# 24_LMS2_RX2_BB_ADC.net
KiCad netlist of a schematic drawn in Altium Designer
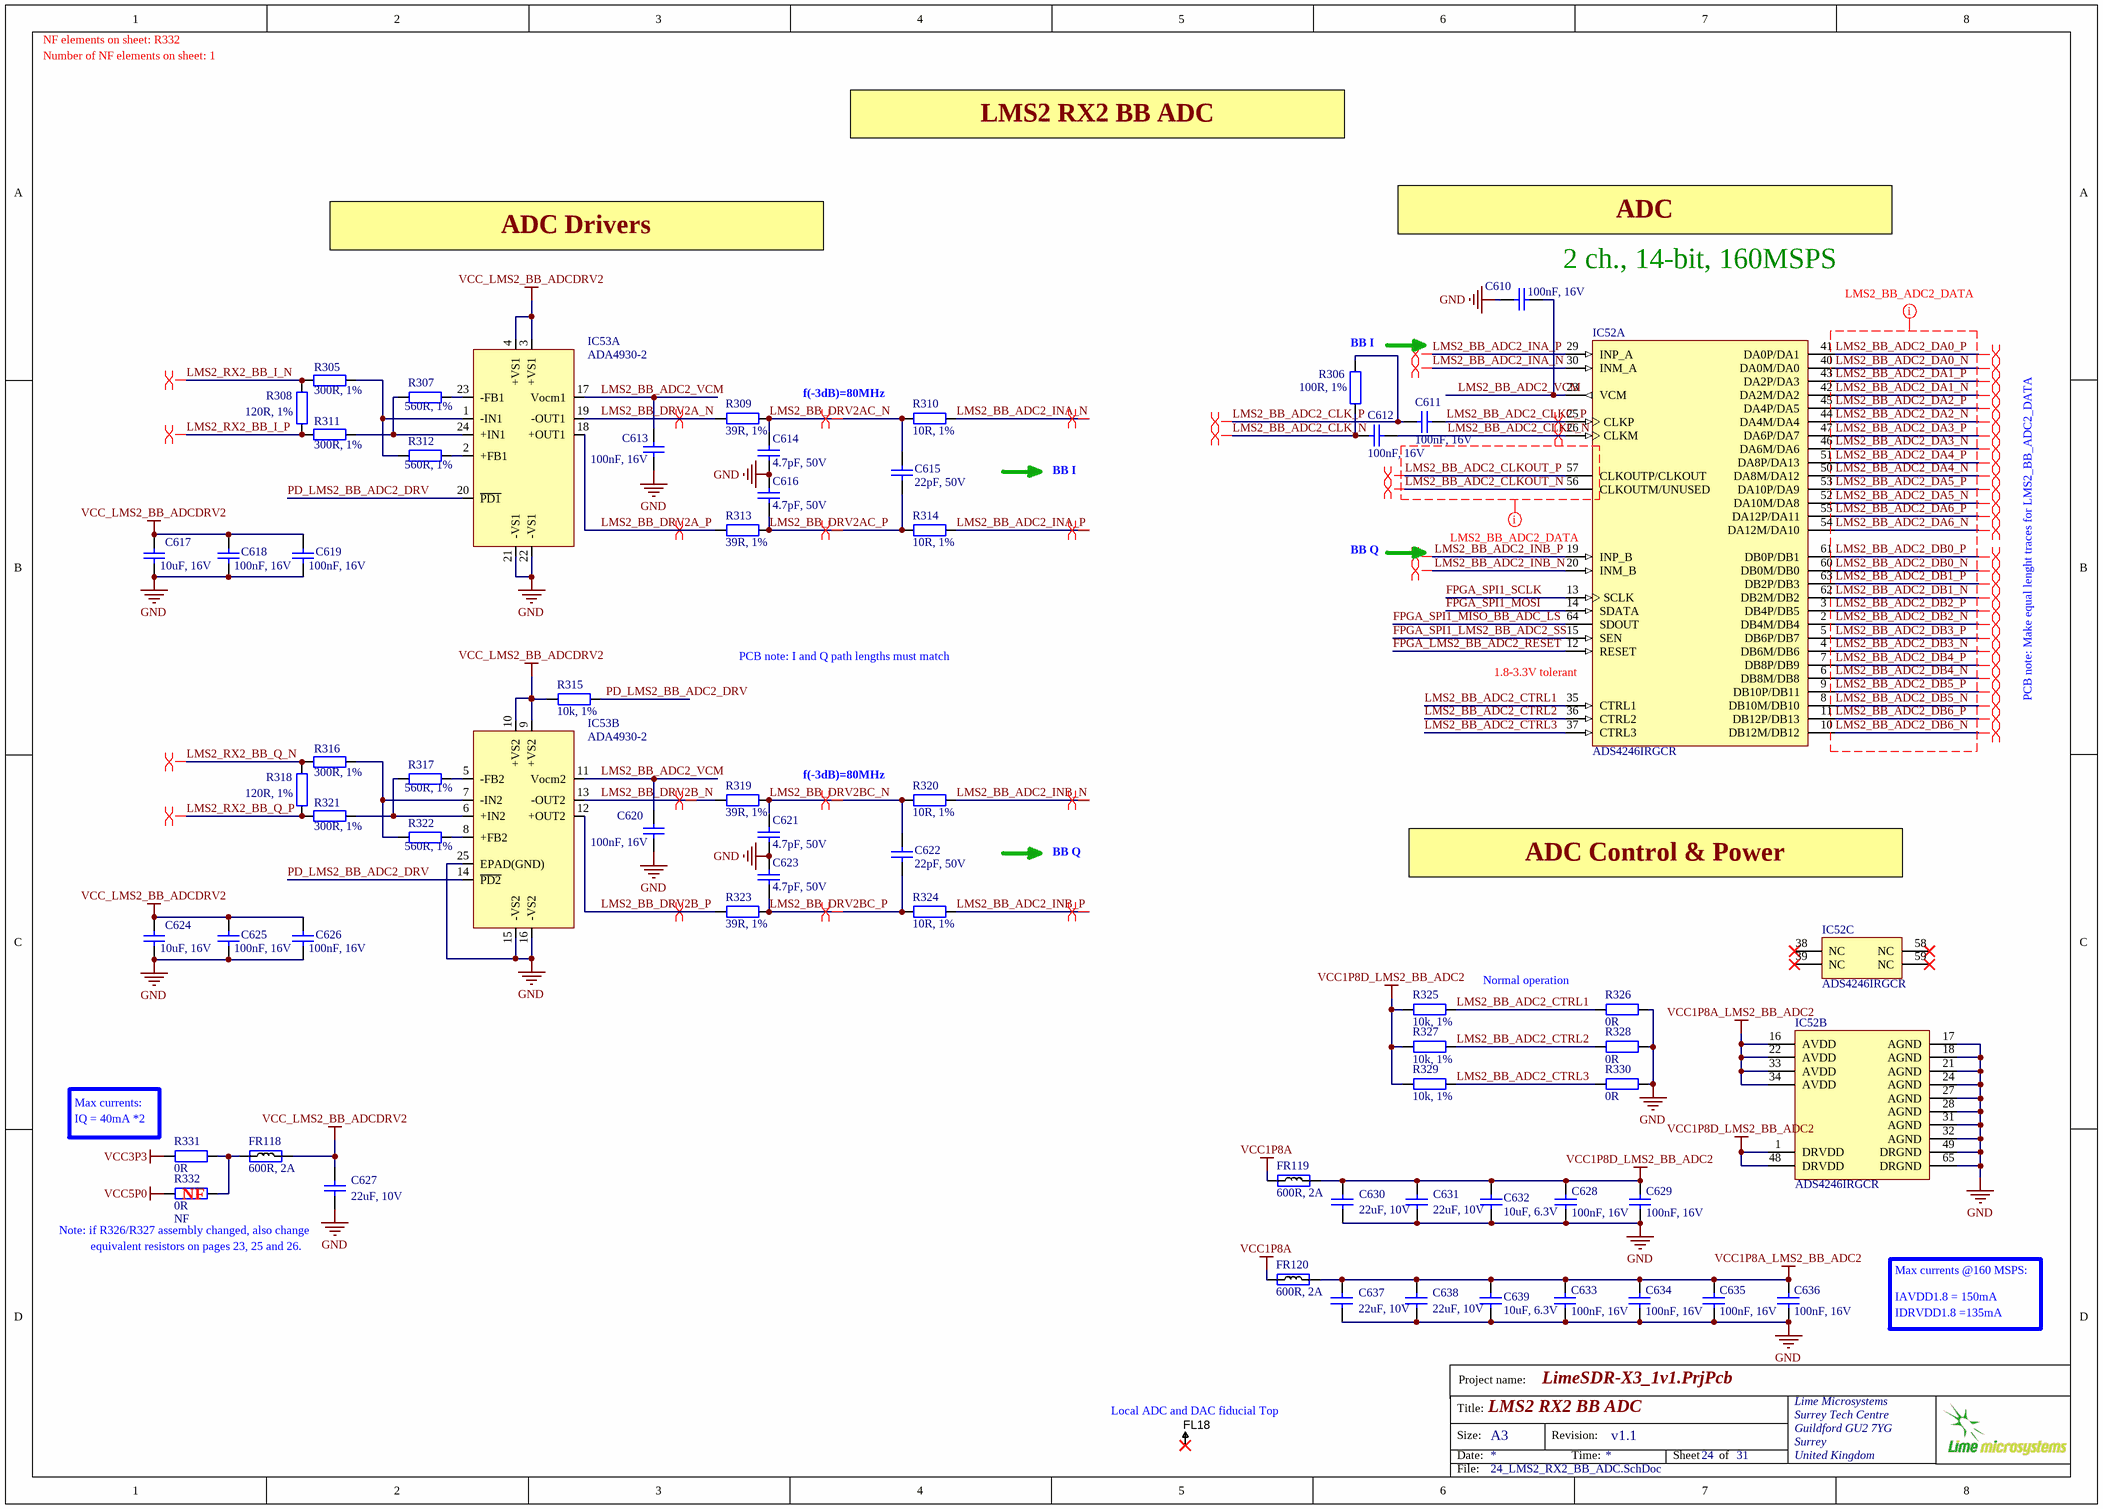
[diagram p0: 24_LMS2_RX2_BB_ADC.SchDoc]

(export (version "E")
  (design (tool "Eeschema 10.0.6"))
  (components
    (comp (ref "C610")
      (value "100nF, 16V")
      (footprint "CAP0402")
      (fields (field (name "TOLERANCE") "10 %") (field (name "MANUFACTURER") "Murata Electronics"))
      (libsource (lib "") (part "Cap_0603_6"))
    )
    (comp (ref "C611")
      (value "100nF, 16V")
      (footprint "CAP0402")
      (fields (field (name "TOLERANCE") "10 %") (field (name "MANUFACTURER") "Murata Electronics"))
      (libsource (lib "") (part "Cap_0603_6"))
    )
    (comp (ref "C612")
      (value "100nF, 16V")
      (footprint "CAP0402")
      (fields (field (name "TOLERANCE") "10 %") (field (name "MANUFACTURER") "Murata Electronics"))
      (libsource (lib "LimeFPGAboard_schLib") (part "Cap_0603"))
    )
    (comp (ref "C613")
      (value "100nF, 16V")
      (footprint "CAP0402")
      (fields (field (name "TOLERANCE") "10 %") (field (name "MANUFACTURER") "Murata Electronics"))
      (libsource (lib "LimeFPGAboard_schLib") (part "Cap_0603"))
    )
    (comp (ref "C614")
      (value "4.7pF, 50V")
      (footprint "CAP0402")
      (fields (field (name "MANUFACTURER") "MURATA"))
      (libsource (lib "LimeMicroAltiumLib_schLib") (part "Cap_0402"))
    )
    (comp (ref "C615")
      (value "22pF, 50V")
      (footprint "CAP0402")
      (fields (field (name "TOLERANCE") "±5%") (field (name "MANUFACTURER") "Yageo"))
      (libsource (lib "") (part "Cap_0402_1"))
    )
    (comp (ref "C616")
      (value "4.7pF, 50V")
      (footprint "CAP0402")
      (fields (field (name "MANUFACTURER") "MURATA"))
      (libsource (lib "LimeMicroAltiumLib_schLib") (part "Cap_0402"))
    )
    (comp (ref "C617")
      (value "10uF, 16V")
      (footprint "CAP0603")
      (fields (field (name "MANUFACTURER") "Yageo") (field (name "TOLERANCE") "±20%"))
      (libsource (lib "LimeMicroAltiumLib_schLib") (part "Cap_0603"))
    )
    (comp (ref "C618")
      (value "100nF, 16V")
      (footprint "CAP0402")
      (fields (field (name "TOLERANCE") "10 %") (field (name "MANUFACTURER") "Murata Electronics"))
      (libsource (lib "LimeFPGAboard_schLib") (part "Cap_0603"))
    )
    (comp (ref "C619")
      (value "100nF, 16V")
      (footprint "CAP0402")
      (fields (field (name "TOLERANCE") "10 %") (field (name "MANUFACTURER") "Murata Electronics"))
      (libsource (lib "LimeFPGAboard_schLib") (part "Cap_0603"))
    )
    (comp (ref "C620")
      (value "100nF, 16V")
      (footprint "CAP0402")
      (fields (field (name "TOLERANCE") "10 %") (field (name "MANUFACTURER") "Murata Electronics"))
      (libsource (lib "") (part "Cap_0603_5"))
    )
    (comp (ref "C621")
      (value "4.7pF, 50V")
      (footprint "CAP0402")
      (fields (field (name "MANUFACTURER") "MURATA"))
      (libsource (lib "LimeMicroAltiumLib_schLib") (part "Cap_0402"))
    )
    (comp (ref "C622")
      (value "22pF, 50V")
      (footprint "CAP0402")
      (fields (field (name "TOLERANCE") "±5%") (field (name "MANUFACTURER") "Yageo"))
      (libsource (lib "") (part "Cap_0402_1"))
    )
    (comp (ref "C623")
      (value "4.7pF, 50V")
      (footprint "CAP0402")
      (fields (field (name "MANUFACTURER") "MURATA"))
      (libsource (lib "LimeMicroAltiumLib_schLib") (part "Cap_0402"))
    )
    (comp (ref "C624")
      (value "10uF, 16V")
      (footprint "CAP0603")
      (fields (field (name "MANUFACTURER") "Yageo") (field (name "TOLERANCE") "±20%"))
      (libsource (lib "LimeMicroAltiumLib_schLib") (part "Cap_0603"))
    )
    (comp (ref "C625")
      (value "100nF, 16V")
      (footprint "CAP0402")
      (fields (field (name "TOLERANCE") "10 %") (field (name "MANUFACTURER") "Murata Electronics"))
      (libsource (lib "LimeFPGAboard_schLib") (part "Cap_0603"))
    )
    (comp (ref "C626")
      (value "100nF, 16V")
      (footprint "CAP0402")
      (fields (field (name "TOLERANCE") "10 %") (field (name "MANUFACTURER") "Murata Electronics"))
      (libsource (lib "LimeFPGAboard_schLib") (part "Cap_0603"))
    )
    (comp (ref "C627")
      (value "22uF, 10V")
      (footprint "CAP0603")
      (fields (field (name "TOLERANCE") "20 %") (field (name "MANUFACTURER") "TDK Corporation"))
      (libsource (lib "") (part "Cap_0603_3"))
    )
    (comp (ref "C628")
      (value "100nF, 16V")
      (footprint "CAP0402")
      (fields (field (name "TOLERANCE") "10 %") (field (name "MANUFACTURER") "Murata Electronics"))
      (libsource (lib "") (part "Cap_0603_1"))
    )
    (comp (ref "C629")
      (value "100nF, 16V")
      (footprint "CAP0402")
      (fields (field (name "TOLERANCE") "10 %") (field (name "MANUFACTURER") "Murata Electronics"))
      (libsource (lib "") (part "Cap_0603_1"))
    )
    (comp (ref "C630")
      (value "22uF, 10V")
      (footprint "CAP0603")
      (fields (field (name "TOLERANCE") "20 %") (field (name "MANUFACTURER") "TDK Corporation"))
      (libsource (lib "") (part "Cap_0603_1"))
    )
    (comp (ref "C631")
      (value "22uF, 10V")
      (footprint "CAP0603")
      (fields (field (name "TOLERANCE") "20 %") (field (name "MANUFACTURER") "TDK Corporation"))
      (libsource (lib "") (part "Cap_0603_1"))
    )
    (comp (ref "C632")
      (value "10uF, 6.3V")
      (footprint "CAP0603")
      (fields (field (name "TOLERANCE") "±20%") (field (name "MANUFACTURER") "Yageo"))
      (libsource (lib "") (part "Cap_0603_7"))
    )
    (comp (ref "C633")
      (value "100nF, 16V")
      (footprint "CAP0402")
      (fields (field (name "TOLERANCE") "10 %") (field (name "MANUFACTURER") "Murata Electronics"))
      (libsource (lib "") (part "Cap_0603_2"))
    )
    (comp (ref "C634")
      (value "100nF, 16V")
      (footprint "CAP0402")
      (fields (field (name "TOLERANCE") "10 %") (field (name "MANUFACTURER") "Murata Electronics"))
      (libsource (lib "") (part "Cap_0603_2"))
    )
    (comp (ref "C635")
      (value "100nF, 16V")
      (footprint "CAP0402")
      (fields (field (name "TOLERANCE") "10 %") (field (name "MANUFACTURER") "Murata Electronics"))
      (libsource (lib "") (part "Cap_0603_2"))
    )
    (comp (ref "C636")
      (value "100nF, 16V")
      (footprint "CAP0402")
      (fields (field (name "TOLERANCE") "10 %") (field (name "MANUFACTURER") "Murata Electronics"))
      (libsource (lib "") (part "Cap_0603_2"))
    )
    (comp (ref "C637")
      (value "22uF, 10V")
      (footprint "CAP0603")
      (fields (field (name "TOLERANCE") "20 %") (field (name "MANUFACTURER") "TDK Corporation"))
      (libsource (lib "") (part "Cap_0603_2"))
    )
    (comp (ref "C638")
      (value "22uF, 10V")
      (footprint "CAP0603")
      (fields (field (name "TOLERANCE") "20 %") (field (name "MANUFACTURER") "TDK Corporation"))
      (libsource (lib "") (part "Cap_0603_2"))
    )
    (comp (ref "C639")
      (value "10uF, 6.3V")
      (footprint "CAP0603")
      (fields (field (name "TOLERANCE") "±20%") (field (name "MANUFACTURER") "Yageo"))
      (libsource (lib "") (part "Cap_0603_4"))
    )
    (comp (ref "FL18")
      (value "Fiducial")
      (footprint "Fiducial_local")
      (libsource (lib "LimeMicroAltiumLib_schLib") (part "Fiducial"))
    )
    (comp (ref "FR118")
      (value "600R, 2A")
      (footprint "RES0805")
      (fields (field (name "MANUFACTURER") "TDK Corporation"))
      (libsource (lib "LimeMicroAltiumLib_schLib") (part "Ferrite"))
    )
    (comp (ref "FR119")
      (value "600R, 2A")
      (footprint "RES0805")
      (fields (field (name "MANUFACTURER") "TDK Corporation"))
      (libsource (lib "LimeFPGAboard_schLib") (part "Ferrite"))
    )
    (comp (ref "FR120")
      (value "600R, 2A")
      (footprint "RES0805")
      (fields (field (name "MANUFACTURER") "TDK Corporation"))
      (libsource (lib "LimeFPGAboard_schLib") (part "Ferrite"))
    )
    (comp (ref "IC52")
      (value "ADS4246IRGCR")
      (footprint "TI-RGC64-7400X7400TP_V")
      (description "14-Bit 160 MSPS Dual Low Power ADC, -40 to 85 degC, 64-pin QFN (RGC64), Green (RoHS & no Sb/Br)")
      (fields (field (name "MANUFACTURER") "Texas Instruments"))
      (libsource (lib "") (part "ADS4246IRGCR_1"))
    )
    (comp (ref "IC53")
      (value "ADA4930-2")
      (footprint "ADA4930-2_LFCSP-24")
      (fields (field (name "MANUFACTURER") "Analog Devices Inc."))
      (libsource (lib "") (part "ADA4930-2_1"))
    )
    (comp (ref "R305")
      (value "300R, 1%")
      (footprint "RES0402")
      (fields (field (name "TOLERANCE") "±1%") (field (name "MANUFACTURER") "Vishay Dale"))
      (libsource (lib "LimeFPGAboard_schLib") (part "Res_0402"))
    )
    (comp (ref "R306")
      (value "100R, 1%")
      (footprint "RES0402")
      (fields (field (name "TOLERANCE") "±1%") (field (name "MANUFACTURER") "Stackpole Electronics Inc."))
      (libsource (lib "LimeFPGAboard_schLib") (part "Res_0402"))
    )
    (comp (ref "R307")
      (value "560R, 1%")
      (footprint "RES0402")
      (fields (field (name "TOLERANCE") "±1%") (field (name "MANUFACTURER") "Vishay Dale"))
      (libsource (lib "LimeFPGAboard_schLib") (part "Res_0402"))
    )
    (comp (ref "R308")
      (value "120R, 1%")
      (footprint "RES0402")
      (fields (field (name "MANUFACTURER") "Yageo") (field (name "TOLERANCE") "1%"))
      (libsource (lib "") (part "Res_0402_1"))
    )
    (comp (ref "R309")
      (value "39R, 1%")
      (footprint "RES0402")
      (fields (field (name "MANUFACTURER") "Yageo") (field (name "TOLERANCE") "1%"))
      (libsource (lib "LimeMicroAltiumLib_schLib") (part "Res_0402"))
    )
    (comp (ref "R310")
      (value "10R, 1%")
      (footprint "RES0402")
      (fields (field (name "TOLERANCE") "1%"))
      (libsource (lib "LimeMicroAltiumLib_schLib") (part "Res_0402"))
    )
    (comp (ref "R311")
      (value "300R, 1%")
      (footprint "RES0402")
      (fields (field (name "TOLERANCE") "±1%") (field (name "MANUFACTURER") "Vishay Dale"))
      (libsource (lib "LimeFPGAboard_schLib") (part "Res_0402"))
    )
    (comp (ref "R312")
      (value "560R, 1%")
      (footprint "RES0402")
      (fields (field (name "TOLERANCE") "±1%") (field (name "MANUFACTURER") "Vishay Dale"))
      (libsource (lib "LimeFPGAboard_schLib") (part "Res_0402"))
    )
    (comp (ref "R313")
      (value "39R, 1%")
      (footprint "RES0402")
      (fields (field (name "MANUFACTURER") "Yageo") (field (name "TOLERANCE") "1%"))
      (libsource (lib "LimeMicroAltiumLib_schLib") (part "Res_0402"))
    )
    (comp (ref "R314")
      (value "10R, 1%")
      (footprint "RES0402")
      (fields (field (name "TOLERANCE") "1%"))
      (libsource (lib "LimeMicroAltiumLib_schLib") (part "Res_0402"))
    )
    (comp (ref "R315")
      (value "10k, 1%")
      (footprint "RES0402")
      (fields (field (name "MANUFACTURER") "Yageo") (field (name "TOLERANCE") "±1%"))
      (libsource (lib "LimeMicroAltiumLib_schLib") (part "Res_0402"))
    )
    (comp (ref "R316")
      (value "300R, 1%")
      (footprint "RES0402")
      (fields (field (name "TOLERANCE") "±1%") (field (name "MANUFACTURER") "Vishay Dale"))
      (libsource (lib "LimeFPGAboard_schLib") (part "Res_0402"))
    )
    (comp (ref "R317")
      (value "560R, 1%")
      (footprint "RES0402")
      (fields (field (name "TOLERANCE") "±1%") (field (name "MANUFACTURER") "Vishay Dale"))
      (libsource (lib "LimeFPGAboard_schLib") (part "Res_0402"))
    )
    (comp (ref "R318")
      (value "120R, 1%")
      (footprint "RES0402")
      (fields (field (name "MANUFACTURER") "Yageo") (field (name "TOLERANCE") "1%"))
      (libsource (lib "") (part "Res_0402_1"))
    )
    (comp (ref "R319")
      (value "39R, 1%")
      (footprint "RES0402")
      (fields (field (name "MANUFACTURER") "Yageo") (field (name "TOLERANCE") "1%"))
      (libsource (lib "LimeMicroAltiumLib_schLib") (part "Res_0402"))
    )
    (comp (ref "R320")
      (value "10R, 1%")
      (footprint "RES0402")
      (fields (field (name "TOLERANCE") "1%"))
      (libsource (lib "LimeMicroAltiumLib_schLib") (part "Res_0402"))
    )
    (comp (ref "R321")
      (value "300R, 1%")
      (footprint "RES0402")
      (fields (field (name "TOLERANCE") "±1%") (field (name "MANUFACTURER") "Vishay Dale"))
      (libsource (lib "LimeFPGAboard_schLib") (part "Res_0402"))
    )
    (comp (ref "R322")
      (value "560R, 1%")
      (footprint "RES0402")
      (fields (field (name "TOLERANCE") "±1%") (field (name "MANUFACTURER") "Vishay Dale"))
      (libsource (lib "LimeFPGAboard_schLib") (part "Res_0402"))
    )
    (comp (ref "R323")
      (value "39R, 1%")
      (footprint "RES0402")
      (fields (field (name "MANUFACTURER") "Yageo") (field (name "TOLERANCE") "1%"))
      (libsource (lib "LimeMicroAltiumLib_schLib") (part "Res_0402"))
    )
    (comp (ref "R324")
      (value "10R, 1%")
      (footprint "RES0402")
      (fields (field (name "TOLERANCE") "1%"))
      (libsource (lib "LimeMicroAltiumLib_schLib") (part "Res_0402"))
    )
    (comp (ref "R325")
      (value "10k, 1%")
      (footprint "RES0402")
      (fields (field (name "MANUFACTURER") "Yageo") (field (name "TOLERANCE") "±1%"))
      (libsource (lib "LimeMicroAltiumLib_schLib") (part "Res_0402"))
    )
    (comp (ref "R326")
      (value "0R")
      (footprint "RES0402")
      (fields (field (name "MANUFACTURER") "Yageo"))
      (libsource (lib "LimeFPGAboard_schLib") (part "Res_0402"))
    )
    (comp (ref "R327")
      (value "10k, 1%")
      (footprint "RES0402")
      (fields (field (name "MANUFACTURER") "Yageo") (field (name "TOLERANCE") "±1%"))
      (libsource (lib "LimeMicroAltiumLib_schLib") (part "Res_0402"))
    )
    (comp (ref "R328")
      (value "0R")
      (footprint "RES0402")
      (fields (field (name "MANUFACTURER") "Yageo"))
      (libsource (lib "LimeFPGAboard_schLib") (part "Res_0402"))
    )
    (comp (ref "R329")
      (value "10k, 1%")
      (footprint "RES0402")
      (fields (field (name "MANUFACTURER") "Yageo") (field (name "TOLERANCE") "±1%"))
      (libsource (lib "LimeMicroAltiumLib_schLib") (part "Res_0402"))
    )
    (comp (ref "R330")
      (value "0R")
      (footprint "RES0402")
      (fields (field (name "MANUFACTURER") "Yageo"))
      (libsource (lib "LimeFPGAboard_schLib") (part "Res_0402"))
    )
    (comp (ref "R331")
      (value "0R")
      (footprint "RES0402")
      (fields (field (name "MANUFACTURER") "Yageo") (field (name "TOLERANCE") "Jumper"))
      (libsource (lib "LimeMicroAltiumLib_schLib") (part "Res_0402"))
    )
    (comp (ref "R332")
      (value "0R")
      (footprint "RES0402")
      (fields
        (field (name "ASSEMBLY INFO") "NF")
        (field (name "MANUFACTURER") "Yageo")
        (field (name "TOLERANCE") "Jumper")
      )
      (libsource (lib "LimeMicroAltiumLib_schLib") (part "Res_0402"))
    )
  )
  (nets
    (net (code "1") (name "/FPGA_LMS2_BB_ADC2_RESET") (class "Default")
      (node (ref "IC52") (pin "12") (pinfunction "RESET_12") (pintype "input"))
    )
    (net (code "2") (name "/FPGA_SPI1_LMS2_BB_ADC2_SS") (class "Default")
      (node (ref "IC52") (pin "15") (pinfunction "SEN_15") (pintype "input"))
    )
    (net (code "3") (name "/FPGA_SPI1_MISO_BB_ADC_LS") (class "Default")
      (node (ref "IC52") (pin "64") (pinfunction "SDOUT_64") (pintype "tri_state"))
    )
    (net (code "4") (name "/FPGA_SPI1_MOSI") (class "Default")
      (node (ref "IC52") (pin "14") (pinfunction "SDATA_14") (pintype "input"))
    )
    (net (code "5") (name "/FPGA_SPI1_SCLK") (class "Default")
      (node (ref "IC52") (pin "13") (pinfunction "SCLK_13") (pintype "input"))
    )
    (net (code "6") (name "/LMS2_BB_ADC2_CLKC_N") (class "Default")
      (node (ref "C612") (pin "1") (pinfunction "1_1") (pintype "passive"))
      (node (ref "IC52") (pin "26") (pinfunction "CLKM_26") (pintype "input"))
    )
    (net (code "7") (name "/LMS2_BB_ADC2_CLKC_P") (class "Default")
      (node (ref "C611") (pin "1") (pinfunction "1_1") (pintype "passive"))
      (node (ref "IC52") (pin "25") (pinfunction "CLKP_25") (pintype "input"))
    )
    (net (code "8") (name "/LMS2_BB_ADC2_CLKOUT_N") (class "Default")
      (node (ref "IC52") (pin "56") (pinfunction "CLKOUTM/UNUSED_56") (pintype "tri_state"))
    )
    (net (code "9") (name "/LMS2_BB_ADC2_CLKOUT_P") (class "Default")
      (node (ref "IC52") (pin "57") (pinfunction "CLKOUTP/CLKOUT_57") (pintype "tri_state"))
    )
    (net (code "10") (name "/LMS2_BB_ADC2_CLK_N") (class "Default")
      (node (ref "C612") (pin "2") (pinfunction "2_2") (pintype "passive"))
      (node (ref "R306") (pin "1") (pinfunction "1_1") (pintype "passive"))
    )
    (net (code "11") (name "/LMS2_BB_ADC2_CLK_P") (class "Default")
      (node (ref "C611") (pin "2") (pinfunction "2_2") (pintype "passive"))
      (node (ref "R306") (pin "2") (pinfunction "2_2") (pintype "passive"))
    )
    (net (code "12") (name "/LMS2_BB_ADC2_CTRL1") (class "Default")
      (node (ref "IC52") (pin "35") (pinfunction "CTRL1_35") (pintype "input"))
      (node (ref "R325") (pin "1") (pinfunction "1_1") (pintype "passive"))
      (node (ref "R326") (pin "2") (pinfunction "2_2") (pintype "passive"))
    )
    (net (code "13") (name "/LMS2_BB_ADC2_CTRL2") (class "Default")
      (node (ref "IC52") (pin "36") (pinfunction "CTRL2_36") (pintype "input"))
      (node (ref "R327") (pin "1") (pinfunction "1_1") (pintype "passive"))
      (node (ref "R328") (pin "2") (pinfunction "2_2") (pintype "passive"))
    )
    (net (code "14") (name "/LMS2_BB_ADC2_CTRL3") (class "Default")
      (node (ref "IC52") (pin "37") (pinfunction "CTRL3_37") (pintype "input"))
      (node (ref "R329") (pin "1") (pinfunction "1_1") (pintype "passive"))
      (node (ref "R330") (pin "2") (pinfunction "2_2") (pintype "passive"))
    )
    (net (code "15") (name "/LMS2_BB_ADC2_DA0_N") (class "Default")
      (node (ref "IC52") (pin "40") (pinfunction "DA0M/DA0_40") (pintype "tri_state"))
    )
    (net (code "16") (name "/LMS2_BB_ADC2_DA0_P") (class "Default")
      (node (ref "IC52") (pin "41") (pinfunction "DA0P/DA1_41") (pintype "tri_state"))
    )
    (net (code "17") (name "/LMS2_BB_ADC2_DA1_N") (class "Default")
      (node (ref "IC52") (pin "42") (pinfunction "DA2M/DA2_42") (pintype "tri_state"))
    )
    (net (code "18") (name "/LMS2_BB_ADC2_DA1_P") (class "Default")
      (node (ref "IC52") (pin "43") (pinfunction "DA2P/DA3_43") (pintype "tri_state"))
    )
    (net (code "19") (name "/LMS2_BB_ADC2_DA2_N") (class "Default")
      (node (ref "IC52") (pin "44") (pinfunction "DA4M/DA4_44") (pintype "tri_state"))
    )
    (net (code "20") (name "/LMS2_BB_ADC2_DA2_P") (class "Default")
      (node (ref "IC52") (pin "45") (pinfunction "DA4P/DA5_45") (pintype "tri_state"))
    )
    (net (code "21") (name "/LMS2_BB_ADC2_DA3_N") (class "Default")
      (node (ref "IC52") (pin "46") (pinfunction "DA6M/DA6_46") (pintype "tri_state"))
    )
    (net (code "22") (name "/LMS2_BB_ADC2_DA3_P") (class "Default")
      (node (ref "IC52") (pin "47") (pinfunction "DA6P/DA7_47") (pintype "tri_state"))
    )
    (net (code "23") (name "/LMS2_BB_ADC2_DA4_N") (class "Default")
      (node (ref "IC52") (pin "50") (pinfunction "DA8M/DA12_50") (pintype "tri_state"))
    )
    (net (code "24") (name "/LMS2_BB_ADC2_DA4_P") (class "Default")
      (node (ref "IC52") (pin "51") (pinfunction "DA8P/DA13_51") (pintype "tri_state"))
    )
    (net (code "25") (name "/LMS2_BB_ADC2_DA5_N") (class "Default")
      (node (ref "IC52") (pin "52") (pinfunction "DA10M/DA8_52") (pintype "tri_state"))
    )
    (net (code "26") (name "/LMS2_BB_ADC2_DA5_P") (class "Default")
      (node (ref "IC52") (pin "53") (pinfunction "DA10P/DA9_53") (pintype "tri_state"))
    )
    (net (code "27") (name "/LMS2_BB_ADC2_DA6_N") (class "Default")
      (node (ref "IC52") (pin "54") (pinfunction "DA12M/DA10_54") (pintype "tri_state"))
    )
    (net (code "28") (name "/LMS2_BB_ADC2_DA6_P") (class "Default")
      (node (ref "IC52") (pin "55") (pinfunction "DA12P/DA11_55") (pintype "tri_state"))
    )
    (net (code "29") (name "/LMS2_BB_ADC2_DB0_N") (class "Default")
      (node (ref "IC52") (pin "60") (pinfunction "DB0M/DB0_60") (pintype "tri_state"))
    )
    (net (code "30") (name "/LMS2_BB_ADC2_DB0_P") (class "Default")
      (node (ref "IC52") (pin "61") (pinfunction "DB0P/DB1_61") (pintype "tri_state"))
    )
    (net (code "31") (name "/LMS2_BB_ADC2_DB1_N") (class "Default")
      (node (ref "IC52") (pin "62") (pinfunction "DB2M/DB2_62") (pintype "tri_state"))
    )
    (net (code "32") (name "/LMS2_BB_ADC2_DB1_P") (class "Default")
      (node (ref "IC52") (pin "63") (pinfunction "DB2P/DB3_63") (pintype "tri_state"))
    )
    (net (code "33") (name "/LMS2_BB_ADC2_DB2_N") (class "Default")
      (node (ref "IC52") (pin "2") (pinfunction "DB4M/DB4_2") (pintype "tri_state"))
    )
    (net (code "34") (name "/LMS2_BB_ADC2_DB2_P") (class "Default")
      (node (ref "IC52") (pin "3") (pinfunction "DB4P/DB5_3") (pintype "tri_state"))
    )
    (net (code "35") (name "/LMS2_BB_ADC2_DB3_N") (class "Default")
      (node (ref "IC52") (pin "4") (pinfunction "DB6M/DB6_4") (pintype "tri_state"))
    )
    (net (code "36") (name "/LMS2_BB_ADC2_DB3_P") (class "Default")
      (node (ref "IC52") (pin "5") (pinfunction "DB6P/DB7_5") (pintype "tri_state"))
    )
    (net (code "37") (name "/LMS2_BB_ADC2_DB4_N") (class "Default")
      (node (ref "IC52") (pin "6") (pinfunction "DB8M/DB8_6") (pintype "tri_state"))
    )
    (net (code "38") (name "/LMS2_BB_ADC2_DB4_P") (class "Default")
      (node (ref "IC52") (pin "7") (pinfunction "DB8P/DB9_7") (pintype "tri_state"))
    )
    (net (code "39") (name "/LMS2_BB_ADC2_DB5_N") (class "Default")
      (node (ref "IC52") (pin "8") (pinfunction "DB10M/DB10_8") (pintype "tri_state"))
    )
    (net (code "40") (name "/LMS2_BB_ADC2_DB5_P") (class "Default")
      (node (ref "IC52") (pin "9") (pinfunction "DB10P/DB11_9") (pintype "tri_state"))
    )
    (net (code "41") (name "/LMS2_BB_ADC2_DB6_N") (class "Default")
      (node (ref "IC52") (pin "10") (pinfunction "DB12M/DB12_10") (pintype "tri_state"))
    )
    (net (code "42") (name "/LMS2_BB_ADC2_DB6_P") (class "Default")
      (node (ref "IC52") (pin "11") (pinfunction "DB12P/DB13_11") (pintype "tri_state"))
    )
    (net (code "43") (name "/LMS2_BB_ADC2_INA_N") (class "Default")
      (node (ref "IC52") (pin "30") (pinfunction "INM_A_30") (pintype "input"))
      (node (ref "R310") (pin "1") (pinfunction "1_1") (pintype "passive"))
    )
    (net (code "44") (name "/LMS2_BB_ADC2_INA_P") (class "Default")
      (node (ref "IC52") (pin "29") (pinfunction "INP_A_29") (pintype "input"))
      (node (ref "R314") (pin "1") (pinfunction "1_1") (pintype "passive"))
    )
    (net (code "45") (name "/LMS2_BB_ADC2_INB_N") (class "Default")
      (node (ref "IC52") (pin "20") (pinfunction "INM_B_20") (pintype "input"))
      (node (ref "R320") (pin "1") (pinfunction "1_1") (pintype "passive"))
    )
    (net (code "46") (name "/LMS2_BB_ADC2_INB_P") (class "Default")
      (node (ref "IC52") (pin "19") (pinfunction "INP_B_19") (pintype "input"))
      (node (ref "R324") (pin "1") (pinfunction "1_1") (pintype "passive"))
    )
    (net (code "47") (name "/LMS2_BB_ADC2_VCM") (class "Default")
      (node (ref "C610") (pin "2") (pinfunction "2_2") (pintype "passive"))
      (node (ref "C613") (pin "1") (pinfunction "1_1") (pintype "passive"))
      (node (ref "C620") (pin "1") (pinfunction "1_1") (pintype "passive"))
      (node (ref "IC52") (pin "23") (pinfunction "VCM_23") (pintype "output"))
      (node (ref "IC53") (pin "11") (pinfunction "Vocm2_11") (pintype "input"))
      (node (ref "IC53") (pin "17") (pinfunction "Vocm1_17") (pintype "input"))
    )
    (net (code "48") (name "/LMS2_BB_DRV2AC_N") (class "Default")
      (node (ref "C614") (pin "1") (pinfunction "1_1") (pintype "passive"))
      (node (ref "C615") (pin "1") (pinfunction "1_1") (pintype "passive"))
      (node (ref "R309") (pin "1") (pinfunction "1_1") (pintype "passive"))
      (node (ref "R310") (pin "2") (pinfunction "2_2") (pintype "passive"))
    )
    (net (code "49") (name "/LMS2_BB_DRV2AC_P") (class "Default")
      (node (ref "C615") (pin "2") (pinfunction "2_2") (pintype "passive"))
      (node (ref "C616") (pin "2") (pinfunction "2_2") (pintype "passive"))
      (node (ref "R313") (pin "1") (pinfunction "1_1") (pintype "passive"))
      (node (ref "R314") (pin "2") (pinfunction "2_2") (pintype "passive"))
    )
    (net (code "50") (name "/LMS2_BB_DRV2A_N") (class "Default")
      (node (ref "IC53") (pin "19") (pinfunction "-OUT1_19") (pintype "output"))
      (node (ref "R309") (pin "2") (pinfunction "2_2") (pintype "passive"))
    )
    (net (code "51") (name "/LMS2_BB_DRV2A_P") (class "Default")
      (node (ref "IC53") (pin "18") (pinfunction "+OUT1_18") (pintype "output"))
      (node (ref "R313") (pin "2") (pinfunction "2_2") (pintype "passive"))
    )
    (net (code "52") (name "/LMS2_BB_DRV2BC_N") (class "Default")
      (node (ref "C621") (pin "1") (pinfunction "1_1") (pintype "passive"))
      (node (ref "C622") (pin "1") (pinfunction "1_1") (pintype "passive"))
      (node (ref "R319") (pin "1") (pinfunction "1_1") (pintype "passive"))
      (node (ref "R320") (pin "2") (pinfunction "2_2") (pintype "passive"))
    )
    (net (code "53") (name "/LMS2_BB_DRV2BC_P") (class "Default")
      (node (ref "C622") (pin "2") (pinfunction "2_2") (pintype "passive"))
      (node (ref "C623") (pin "2") (pinfunction "2_2") (pintype "passive"))
      (node (ref "R323") (pin "1") (pinfunction "1_1") (pintype "passive"))
      (node (ref "R324") (pin "2") (pinfunction "2_2") (pintype "passive"))
    )
    (net (code "54") (name "/LMS2_BB_DRV2B_N") (class "Default")
      (node (ref "IC53") (pin "13") (pinfunction "-OUT2_13") (pintype "output"))
      (node (ref "R319") (pin "2") (pinfunction "2_2") (pintype "passive"))
    )
    (net (code "55") (name "/LMS2_BB_DRV2B_P") (class "Default")
      (node (ref "IC53") (pin "12") (pinfunction "+OUT2_12") (pintype "output"))
      (node (ref "R323") (pin "2") (pinfunction "2_2") (pintype "passive"))
    )
    (net (code "56") (name "/LMS2_RX2_BB_I_N") (class "Default")
      (node (ref "R305") (pin "2") (pinfunction "2_2") (pintype "passive"))
      (node (ref "R308") (pin "2") (pinfunction "2_2") (pintype "passive"))
    )
    (net (code "57") (name "/LMS2_RX2_BB_I_P") (class "Default")
      (node (ref "R308") (pin "1") (pinfunction "1_1") (pintype "passive"))
      (node (ref "R311") (pin "2") (pinfunction "2_2") (pintype "passive"))
    )
    (net (code "58") (name "/LMS2_RX2_BB_Q_N") (class "Default")
      (node (ref "R316") (pin "2") (pinfunction "2_2") (pintype "passive"))
      (node (ref "R318") (pin "2") (pinfunction "2_2") (pintype "passive"))
    )
    (net (code "59") (name "/LMS2_RX2_BB_Q_P") (class "Default")
      (node (ref "R318") (pin "1") (pinfunction "1_1") (pintype "passive"))
      (node (ref "R321") (pin "2") (pinfunction "2_2") (pintype "passive"))
    )
    (net (code "60") (name "/PD_LMS2_BB_ADC2_DRV") (class "Default")
      (node (ref "IC53") (pin "14") (pinfunction "~{PD2}_14") (pintype "input"))
      (node (ref "IC53") (pin "20") (pinfunction "~{PD1}_20") (pintype "input"))
      (node (ref "R315") (pin "1") (pinfunction "1_1") (pintype "passive"))
    )
    (net (code "61") (name "GND") (class "Default")
      (node (ref "C610") (pin "1") (pinfunction "1_1") (pintype "passive"))
      (node (ref "C613") (pin "2") (pinfunction "2_2") (pintype "passive"))
      (node (ref "C614") (pin "2") (pinfunction "2_2") (pintype "passive"))
      (node (ref "C616") (pin "1") (pinfunction "1_1") (pintype "passive"))
      (node (ref "C617") (pin "1") (pinfunction "1_1") (pintype "passive"))
      (node (ref "C618") (pin "2") (pinfunction "2_2") (pintype "passive"))
      (node (ref "C619") (pin "2") (pinfunction "2_2") (pintype "passive"))
      (node (ref "C620") (pin "2") (pinfunction "2_2") (pintype "passive"))
      (node (ref "C621") (pin "2") (pinfunction "2_2") (pintype "passive"))
      (node (ref "C623") (pin "1") (pinfunction "1_1") (pintype "passive"))
      (node (ref "C624") (pin "1") (pinfunction "1_1") (pintype "passive"))
      (node (ref "C625") (pin "2") (pinfunction "2_2") (pintype "passive"))
      (node (ref "C626") (pin "2") (pinfunction "2_2") (pintype "passive"))
      (node (ref "C627") (pin "1") (pinfunction "1_1") (pintype "passive"))
      (node (ref "C628") (pin "1") (pinfunction "1_1") (pintype "passive"))
      (node (ref "C629") (pin "1") (pinfunction "1_1") (pintype "passive"))
      (node (ref "C630") (pin "1") (pinfunction "1_1") (pintype "passive"))
      (node (ref "C631") (pin "1") (pinfunction "1_1") (pintype "passive"))
      (node (ref "C632") (pin "2") (pinfunction "2_2") (pintype "passive"))
      (node (ref "C633") (pin "1") (pinfunction "1_1") (pintype "passive"))
      (node (ref "C634") (pin "1") (pinfunction "1_1") (pintype "passive"))
      (node (ref "C635") (pin "1") (pinfunction "1_1") (pintype "passive"))
      (node (ref "C636") (pin "1") (pinfunction "1_1") (pintype "passive"))
      (node (ref "C637") (pin "1") (pinfunction "1_1") (pintype "passive"))
      (node (ref "C638") (pin "1") (pinfunction "1_1") (pintype "passive"))
      (node (ref "C639") (pin "2") (pinfunction "2_2") (pintype "passive"))
      (node (ref "IC52") (pin "17") (pinfunction "AGND_17") (pintype "power_in"))
      (node (ref "IC52") (pin "18") (pinfunction "AGND_18") (pintype "power_in"))
      (node (ref "IC52") (pin "21") (pinfunction "AGND_21") (pintype "power_in"))
      (node (ref "IC52") (pin "24") (pinfunction "AGND_24") (pintype "power_in"))
      (node (ref "IC52") (pin "27") (pinfunction "AGND_27") (pintype "power_in"))
      (node (ref "IC52") (pin "28") (pinfunction "AGND_28") (pintype "power_in"))
      (node (ref "IC52") (pin "31") (pinfunction "AGND_31") (pintype "power_in"))
      (node (ref "IC52") (pin "32") (pinfunction "AGND_32") (pintype "power_in"))
      (node (ref "IC52") (pin "49") (pinfunction "DRGND_49") (pintype "power_in"))
      (node (ref "IC52") (pin "65") (pinfunction "DRGND_65") (pintype "power_in"))
      (node (ref "IC53") (pin "15") (pinfunction "-VS2_15") (pintype "power_in"))
      (node (ref "IC53") (pin "16") (pinfunction "-VS2_16") (pintype "power_in"))
      (node (ref "IC53") (pin "21") (pinfunction "-VS1_21") (pintype "power_in"))
      (node (ref "IC53") (pin "22") (pinfunction "-VS1_22") (pintype "power_in"))
      (node (ref "IC53") (pin "25") (pinfunction "EPAD(GND)_25") (pintype "passive"))
      (node (ref "R326") (pin "1") (pinfunction "1_1") (pintype "passive"))
      (node (ref "R328") (pin "1") (pinfunction "1_1") (pintype "passive"))
      (node (ref "R330") (pin "1") (pinfunction "1_1") (pintype "passive"))
    )
    (net (code "62") (name "Net-(FR118-Pad1)") (class "Default")
      (node (ref "FR118") (pin "1") (pinfunction "1_1") (pintype "passive"))
      (node (ref "R331") (pin "1") (pinfunction "1_1") (pintype "passive"))
      (node (ref "R332") (pin "1") (pinfunction "1_1") (pintype "passive"))
    )
    (net (code "63") (name "Net-(IC53A-+FB1)") (class "Default")
      (node (ref "IC53") (pin "2") (pinfunction "+FB1_2") (pintype "output"))
      (node (ref "R312") (pin "1") (pinfunction "1_1") (pintype "passive"))
    )
    (net (code "64") (name "Net-(IC53A-+IN1)") (class "Default")
      (node (ref "IC53") (pin "24") (pinfunction "+IN1_24") (pintype "input"))
      (node (ref "R307") (pin "2") (pinfunction "2_2") (pintype "passive"))
      (node (ref "R311") (pin "1") (pinfunction "1_1") (pintype "passive"))
    )
    (net (code "65") (name "Net-(IC53A--FB1)") (class "Default")
      (node (ref "IC53") (pin "23") (pinfunction "-FB1_23") (pintype "output"))
      (node (ref "R307") (pin "1") (pinfunction "1_1") (pintype "passive"))
    )
    (net (code "66") (name "Net-(IC53A--IN1)") (class "Default")
      (node (ref "IC53") (pin "1") (pinfunction "-IN1_1") (pintype "input"))
      (node (ref "R305") (pin "1") (pinfunction "1_1") (pintype "passive"))
      (node (ref "R312") (pin "2") (pinfunction "2_2") (pintype "passive"))
    )
    (net (code "67") (name "Net-(IC53B-+FB2)") (class "Default")
      (node (ref "IC53") (pin "8") (pinfunction "+FB2_8") (pintype "output"))
      (node (ref "R322") (pin "1") (pinfunction "1_1") (pintype "passive"))
    )
    (net (code "68") (name "Net-(IC53B-+IN2)") (class "Default")
      (node (ref "IC53") (pin "6") (pinfunction "+IN2_6") (pintype "input"))
      (node (ref "R317") (pin "2") (pinfunction "2_2") (pintype "passive"))
      (node (ref "R321") (pin "1") (pinfunction "1_1") (pintype "passive"))
    )
    (net (code "69") (name "Net-(IC53B--FB2)") (class "Default")
      (node (ref "IC53") (pin "5") (pinfunction "-FB2_5") (pintype "output"))
      (node (ref "R317") (pin "1") (pinfunction "1_1") (pintype "passive"))
    )
    (net (code "70") (name "Net-(IC53B--IN2)") (class "Default")
      (node (ref "IC53") (pin "7") (pinfunction "-IN2_7") (pintype "input"))
      (node (ref "R316") (pin "1") (pinfunction "1_1") (pintype "passive"))
      (node (ref "R322") (pin "2") (pinfunction "2_2") (pintype "passive"))
    )
    (net (code "71") (name "VCC1P8A") (class "Default")
      (node (ref "FR119") (pin "1") (pinfunction "1_1") (pintype "passive"))
      (node (ref "FR120") (pin "1") (pinfunction "1_1") (pintype "passive"))
    )
    (net (code "72") (name "VCC1P8A_LMS2_BB_ADC2") (class "Default")
      (node (ref "C633") (pin "2") (pinfunction "2_2") (pintype "passive"))
      (node (ref "C634") (pin "2") (pinfunction "2_2") (pintype "passive"))
      (node (ref "C635") (pin "2") (pinfunction "2_2") (pintype "passive"))
      (node (ref "C636") (pin "2") (pinfunction "2_2") (pintype "passive"))
      (node (ref "C637") (pin "2") (pinfunction "2_2") (pintype "passive"))
      (node (ref "C638") (pin "2") (pinfunction "2_2") (pintype "passive"))
      (node (ref "C639") (pin "1") (pinfunction "1_1") (pintype "passive"))
      (node (ref "FR120") (pin "2") (pinfunction "2_2") (pintype "passive"))
      (node (ref "IC52") (pin "16") (pinfunction "AVDD_16") (pintype "power_in"))
      (node (ref "IC52") (pin "22") (pinfunction "AVDD_22") (pintype "power_in"))
      (node (ref "IC52") (pin "33") (pinfunction "AVDD_33") (pintype "power_in"))
      (node (ref "IC52") (pin "34") (pinfunction "AVDD_34") (pintype "power_in"))
    )
    (net (code "73") (name "VCC1P8D_LMS2_BB_ADC2") (class "Default")
      (node (ref "C628") (pin "2") (pinfunction "2_2") (pintype "passive"))
      (node (ref "C629") (pin "2") (pinfunction "2_2") (pintype "passive"))
      (node (ref "C630") (pin "2") (pinfunction "2_2") (pintype "passive"))
      (node (ref "C631") (pin "2") (pinfunction "2_2") (pintype "passive"))
      (node (ref "C632") (pin "1") (pinfunction "1_1") (pintype "passive"))
      (node (ref "FR119") (pin "2") (pinfunction "2_2") (pintype "passive"))
      (node (ref "IC52") (pin "1") (pinfunction "DRVDD_1") (pintype "power_in"))
      (node (ref "IC52") (pin "48") (pinfunction "DRVDD_48") (pintype "power_in"))
      (node (ref "R325") (pin "2") (pinfunction "2_2") (pintype "passive"))
      (node (ref "R327") (pin "2") (pinfunction "2_2") (pintype "passive"))
      (node (ref "R329") (pin "2") (pinfunction "2_2") (pintype "passive"))
    )
    (net (code "74") (name "VCC3P3") (class "Default")
      (node (ref "R331") (pin "2") (pinfunction "2_2") (pintype "passive"))
    )
    (net (code "75") (name "VCC5P0") (class "Default")
      (node (ref "R332") (pin "2") (pinfunction "2_2") (pintype "passive"))
    )
    (net (code "76") (name "VCC_LMS2_BB_ADCDRV2") (class "Default")
      (node (ref "C617") (pin "2") (pinfunction "2_2") (pintype "passive"))
      (node (ref "C618") (pin "1") (pinfunction "1_1") (pintype "passive"))
      (node (ref "C619") (pin "1") (pinfunction "1_1") (pintype "passive"))
      (node (ref "C624") (pin "2") (pinfunction "2_2") (pintype "passive"))
      (node (ref "C625") (pin "1") (pinfunction "1_1") (pintype "passive"))
      (node (ref "C626") (pin "1") (pinfunction "1_1") (pintype "passive"))
      (node (ref "C627") (pin "2") (pinfunction "2_2") (pintype "passive"))
      (node (ref "FR118") (pin "2") (pinfunction "2_2") (pintype "passive"))
      (node (ref "IC53") (pin "10") (pinfunction "+VS2_10") (pintype "power_in"))
      (node (ref "IC53") (pin "3") (pinfunction "+VS1_3") (pintype "power_in"))
      (node (ref "IC53") (pin "4") (pinfunction "+VS1_4") (pintype "power_in"))
      (node (ref "IC53") (pin "9") (pinfunction "+VS2_9") (pintype "power_in"))
      (node (ref "R315") (pin "2") (pinfunction "2_2") (pintype "passive"))
    )
    (net (code "77") (name "unconnected-(FL18-Pad1)") (class "Default")
      (node (ref "FL18") (pin "1") (pintype "passive+no_connect"))
    )
    (net (code "78") (name "unconnected-(IC52C-NC-Pad38)") (class "Default")
      (node (ref "IC52") (pin "38") (pinfunction "NC_38") (pintype "passive+no_connect"))
    )
    (net (code "79") (name "unconnected-(IC52C-NC-Pad39)") (class "Default")
      (node (ref "IC52") (pin "39") (pinfunction "NC_39") (pintype "passive+no_connect"))
    )
    (net (code "80") (name "unconnected-(IC52C-NC-Pad58)") (class "Default")
      (node (ref "IC52") (pin "58") (pinfunction "NC_58") (pintype "passive+no_connect"))
    )
    (net (code "81") (name "unconnected-(IC52C-NC-Pad59)") (class "Default")
      (node (ref "IC52") (pin "59") (pinfunction "NC_59") (pintype "passive+no_connect"))
    )
  )
)
